# LED-controller-4.net
KiCad netlist of a schematic drawn in EAGLE
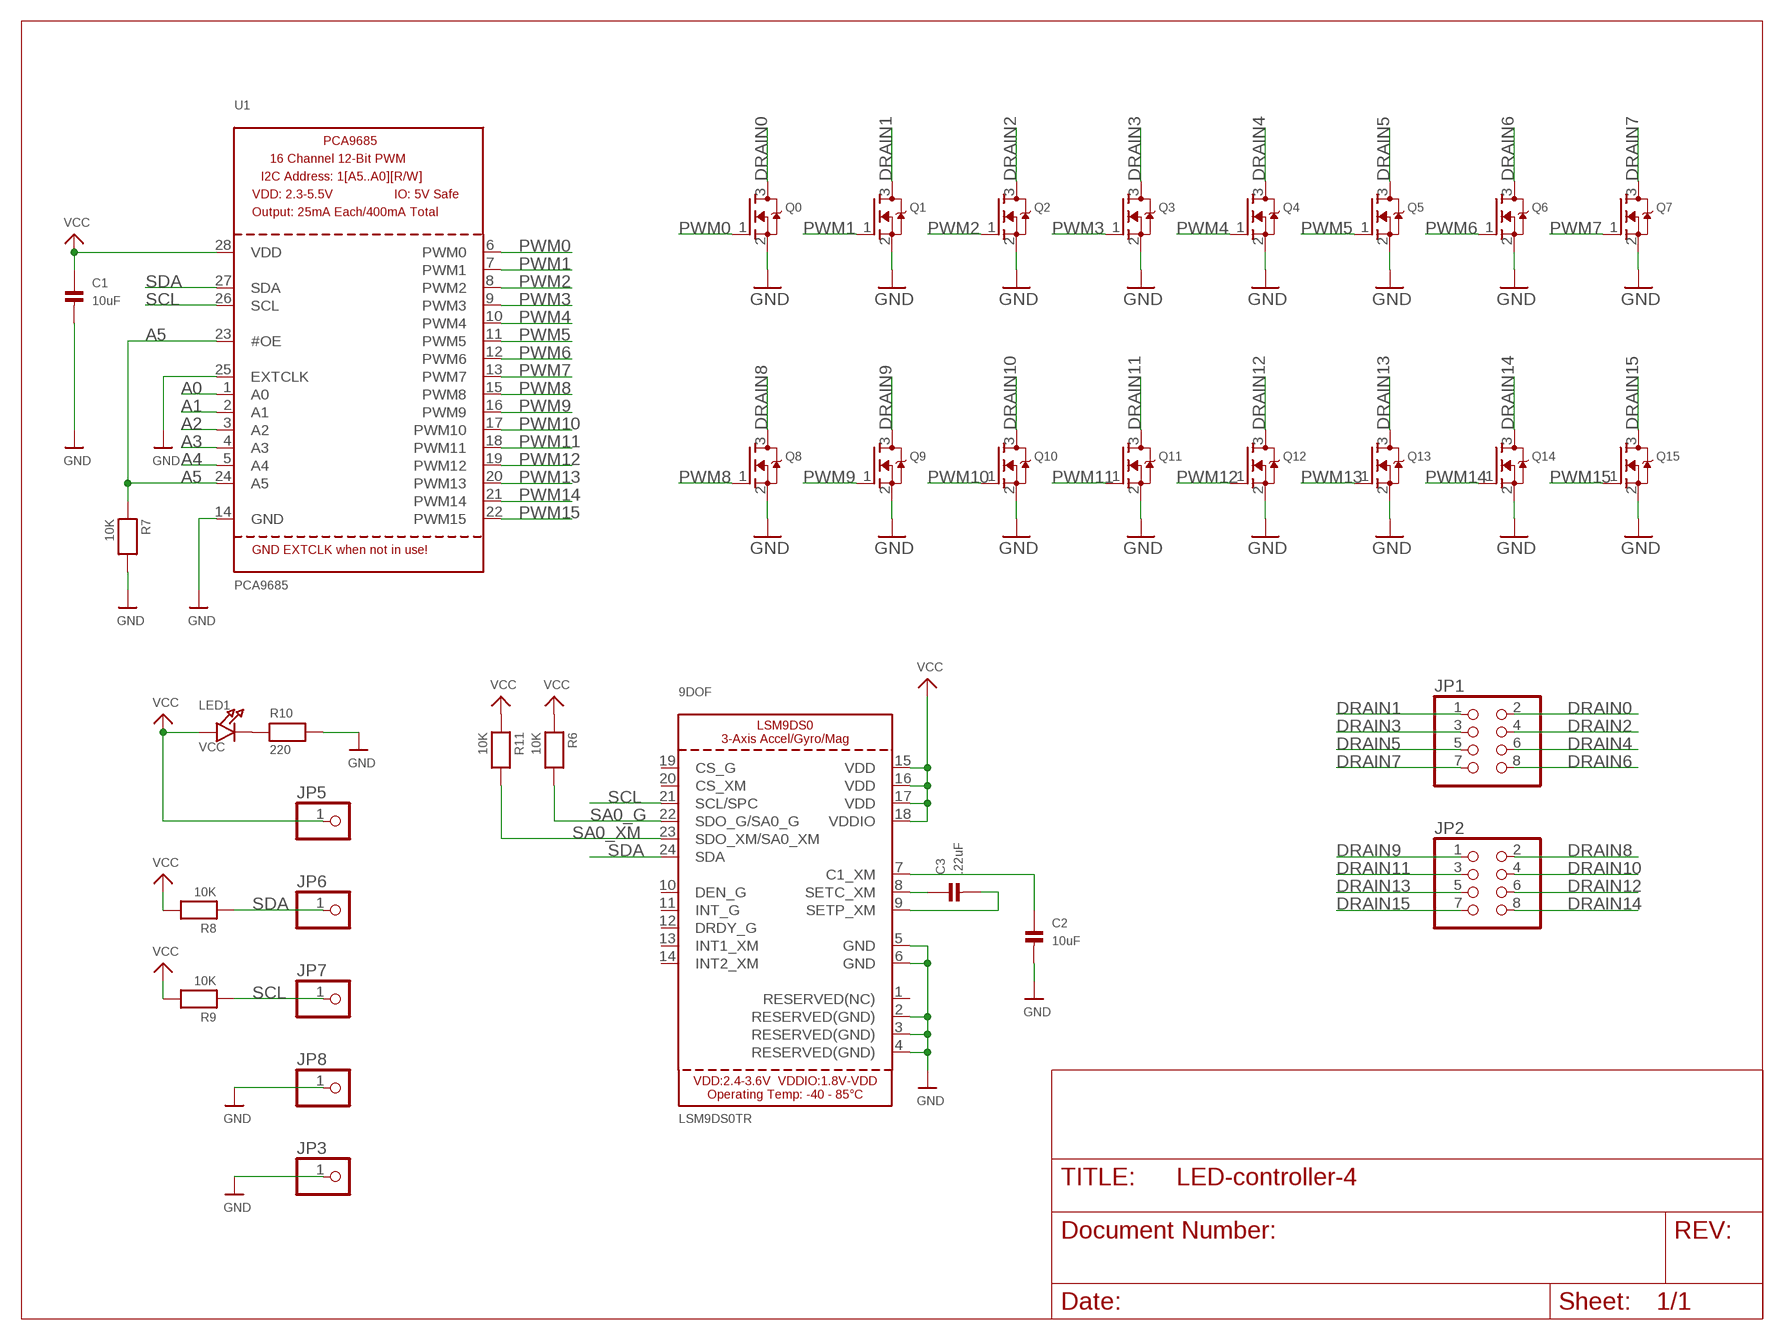
[diagram p0: schematic, sheet 1]

(export (version "E")
  (design (tool "Eeschema 10.0.6"))
  (components
    (comp (ref "9DOF")
      (value "LSM9DS0TR")
      (footprint "eagle-import:LGA24_4X4MM")
      (libsource (lib "eagle-import") (part "LSM9DS0"))
    )
    (comp (ref "C1")
      (value "10uF")
      (footprint "eagle-import:0805")
      (libsource (lib "eagle-import") (part "CAP_CERAMIC0805"))
    )
    (comp (ref "C2")
      (value "10uF")
      (footprint "eagle-import:0805")
      (libsource (lib "eagle-import") (part "CAP_CERAMIC0805"))
    )
    (comp (ref "C3")
      (value ".22uF")
      (footprint "eagle-import:0805")
      (libsource (lib "eagle-import") (part "CAP_CERAMIC0805"))
    )
    (comp (ref "JP1")
      (value "PINHD-2X4")
      (footprint "eagle-import:2X04")
      (libsource (lib "eagle-import") (part "PINHD-2X4"))
    )
    (comp (ref "JP2")
      (value "PINHD-2X4")
      (footprint "eagle-import:2X04")
      (libsource (lib "eagle-import") (part "PINHD-2X4"))
    )
    (comp (ref "JP3")
      (value "PINHD-1X1CB")
      (footprint "eagle-import:1X01-CLEANBIG")
      (libsource (lib "eagle-import") (part "PINHD-1X1CB"))
    )
    (comp (ref "JP5")
      (value "PINHD-1X1CB")
      (footprint "eagle-import:1X01-CLEANBIG")
      (libsource (lib "eagle-import") (part "PINHD-1X1CB"))
    )
    (comp (ref "JP6")
      (value "PINHD-1X1CB")
      (footprint "eagle-import:1X01-CLEANBIG")
      (libsource (lib "eagle-import") (part "PINHD-1X1CB"))
    )
    (comp (ref "JP7")
      (value "PINHD-1X1CB")
      (footprint "eagle-import:1X01-CLEANBIG")
      (libsource (lib "eagle-import") (part "PINHD-1X1CB"))
    )
    (comp (ref "JP8")
      (value "PINHD-1X1CB")
      (footprint "eagle-import:1X01-CLEANBIG")
      (libsource (lib "eagle-import") (part "PINHD-1X1CB"))
    )
    (comp (ref "LED1")
      (value "VCC")
      (footprint "eagle-import:CHIPLED_0805")
      (libsource (lib "eagle-import") (part "LED0805"))
    )
    (comp (ref "Q0")
      (value "MOSFET-NREFLOW")
      (footprint "eagle-import:SOT23")
      (libsource (lib "eagle-import") (part "MOSFET-NREFLOW"))
    )
    (comp (ref "Q1")
      (value "MOSFET-NREFLOW")
      (footprint "eagle-import:SOT23")
      (libsource (lib "eagle-import") (part "MOSFET-NREFLOW"))
    )
    (comp (ref "Q2")
      (value "MOSFET-NREFLOW")
      (footprint "eagle-import:SOT23")
      (libsource (lib "eagle-import") (part "MOSFET-NREFLOW"))
    )
    (comp (ref "Q3")
      (value "MOSFET-NREFLOW")
      (footprint "eagle-import:SOT23")
      (libsource (lib "eagle-import") (part "MOSFET-NREFLOW"))
    )
    (comp (ref "Q4")
      (value "MOSFET-NREFLOW")
      (footprint "eagle-import:SOT23")
      (libsource (lib "eagle-import") (part "MOSFET-NREFLOW"))
    )
    (comp (ref "Q5")
      (value "MOSFET-NREFLOW")
      (footprint "eagle-import:SOT23")
      (libsource (lib "eagle-import") (part "MOSFET-NREFLOW"))
    )
    (comp (ref "Q6")
      (value "MOSFET-NREFLOW")
      (footprint "eagle-import:SOT23")
      (libsource (lib "eagle-import") (part "MOSFET-NREFLOW"))
    )
    (comp (ref "Q7")
      (value "MOSFET-NREFLOW")
      (footprint "eagle-import:SOT23")
      (libsource (lib "eagle-import") (part "MOSFET-NREFLOW"))
    )
    (comp (ref "Q8")
      (value "MOSFET-NREFLOW")
      (footprint "eagle-import:SOT23")
      (libsource (lib "eagle-import") (part "MOSFET-NREFLOW"))
    )
    (comp (ref "Q9")
      (value "MOSFET-NREFLOW")
      (footprint "eagle-import:SOT23")
      (libsource (lib "eagle-import") (part "MOSFET-NREFLOW"))
    )
    (comp (ref "Q10")
      (value "MOSFET-NREFLOW")
      (footprint "eagle-import:SOT23")
      (libsource (lib "eagle-import") (part "MOSFET-NREFLOW"))
    )
    (comp (ref "Q11")
      (value "MOSFET-NREFLOW")
      (footprint "eagle-import:SOT23")
      (libsource (lib "eagle-import") (part "MOSFET-NREFLOW"))
    )
    (comp (ref "Q12")
      (value "MOSFET-NREFLOW")
      (footprint "eagle-import:SOT23")
      (libsource (lib "eagle-import") (part "MOSFET-NREFLOW"))
    )
    (comp (ref "Q13")
      (value "MOSFET-NREFLOW")
      (footprint "eagle-import:SOT23")
      (libsource (lib "eagle-import") (part "MOSFET-NREFLOW"))
    )
    (comp (ref "Q14")
      (value "MOSFET-NREFLOW")
      (footprint "eagle-import:SOT23")
      (libsource (lib "eagle-import") (part "MOSFET-NREFLOW"))
    )
    (comp (ref "Q15")
      (value "MOSFET-NREFLOW")
      (footprint "eagle-import:SOT23")
      (libsource (lib "eagle-import") (part "MOSFET-NREFLOW"))
    )
    (comp (ref "R6")
      (value "10K")
      (footprint "eagle-import:0603")
      (libsource (lib "eagle-import") (part "RESISTOR0603"))
    )
    (comp (ref "R7")
      (value "10K")
      (footprint "eagle-import:0603")
      (libsource (lib "eagle-import") (part "RESISTOR0603"))
    )
    (comp (ref "R8")
      (value "10K")
      (footprint "eagle-import:0603")
      (libsource (lib "eagle-import") (part "RESISTOR0603"))
    )
    (comp (ref "R9")
      (value "10K")
      (footprint "eagle-import:0603")
      (libsource (lib "eagle-import") (part "RESISTOR0603"))
    )
    (comp (ref "R10")
      (value "220")
      (footprint "eagle-import:0603")
      (libsource (lib "eagle-import") (part "RESISTOR0603"))
    )
    (comp (ref "R11")
      (value "10K")
      (footprint "eagle-import:0603")
      (libsource (lib "eagle-import") (part "RESISTOR0603"))
    )
    (comp (ref "U1")
      (value "PCA9685")
      (footprint "eagle-import:TSSOP28")
      (libsource (lib "eagle-import") (part "PCA9685"))
    )
  )
  (nets
    (net (code "1") (name "/A0") (class "Default")
      (node (ref "U1") (pin "1") (pinfunction "A0_1") (pintype "bidirectional"))
    )
    (net (code "2") (name "/A1") (class "Default")
      (node (ref "U1") (pin "2") (pinfunction "A1_2") (pintype "bidirectional"))
    )
    (net (code "3") (name "/A2") (class "Default")
      (node (ref "U1") (pin "3") (pinfunction "A2_3") (pintype "bidirectional"))
    )
    (net (code "4") (name "/A3") (class "Default")
      (node (ref "U1") (pin "4") (pinfunction "A3_4") (pintype "bidirectional"))
    )
    (net (code "5") (name "/A4") (class "Default")
      (node (ref "U1") (pin "5") (pinfunction "A4_5") (pintype "bidirectional"))
    )
    (net (code "6") (name "/A5") (class "Default")
      (node (ref "R7") (pin "1") (pinfunction "1_1") (pintype "passive"))
      (node (ref "U1") (pin "23") (pinfunction "#OE_23") (pintype "input"))
      (node (ref "U1") (pin "24") (pinfunction "A5_24") (pintype "bidirectional"))
    )
    (net (code "7") (name "/DRAIN0") (class "Default")
      (node (ref "JP1") (pin "2") (pinfunction "2_2") (pintype "passive"))
      (node (ref "Q0") (pin "3") (pinfunction "D_3") (pintype "bidirectional"))
    )
    (net (code "8") (name "/DRAIN1") (class "Default")
      (node (ref "JP1") (pin "1") (pinfunction "1_1") (pintype "passive"))
      (node (ref "Q1") (pin "3") (pinfunction "D_3") (pintype "bidirectional"))
    )
    (net (code "9") (name "/DRAIN2") (class "Default")
      (node (ref "JP1") (pin "4") (pinfunction "4_4") (pintype "passive"))
      (node (ref "Q2") (pin "3") (pinfunction "D_3") (pintype "bidirectional"))
    )
    (net (code "10") (name "/DRAIN3") (class "Default")
      (node (ref "JP1") (pin "3") (pinfunction "3_3") (pintype "passive"))
      (node (ref "Q3") (pin "3") (pinfunction "D_3") (pintype "bidirectional"))
    )
    (net (code "11") (name "/DRAIN4") (class "Default")
      (node (ref "JP1") (pin "6") (pinfunction "6_6") (pintype "passive"))
      (node (ref "Q4") (pin "3") (pinfunction "D_3") (pintype "bidirectional"))
    )
    (net (code "12") (name "/DRAIN5") (class "Default")
      (node (ref "JP1") (pin "5") (pinfunction "5_5") (pintype "passive"))
      (node (ref "Q5") (pin "3") (pinfunction "D_3") (pintype "bidirectional"))
    )
    (net (code "13") (name "/DRAIN6") (class "Default")
      (node (ref "JP1") (pin "8") (pinfunction "8_8") (pintype "passive"))
      (node (ref "Q6") (pin "3") (pinfunction "D_3") (pintype "bidirectional"))
    )
    (net (code "14") (name "/DRAIN7") (class "Default")
      (node (ref "JP1") (pin "7") (pinfunction "7_7") (pintype "passive"))
      (node (ref "Q7") (pin "3") (pinfunction "D_3") (pintype "bidirectional"))
    )
    (net (code "15") (name "/DRAIN8") (class "Default")
      (node (ref "JP2") (pin "2") (pinfunction "2_2") (pintype "passive"))
      (node (ref "Q8") (pin "3") (pinfunction "D_3") (pintype "bidirectional"))
    )
    (net (code "16") (name "/DRAIN9") (class "Default")
      (node (ref "JP2") (pin "1") (pinfunction "1_1") (pintype "passive"))
      (node (ref "Q9") (pin "3") (pinfunction "D_3") (pintype "bidirectional"))
    )
    (net (code "17") (name "/DRAIN10") (class "Default")
      (node (ref "JP2") (pin "4") (pinfunction "4_4") (pintype "passive"))
      (node (ref "Q10") (pin "3") (pinfunction "D_3") (pintype "bidirectional"))
    )
    (net (code "18") (name "/DRAIN11") (class "Default")
      (node (ref "JP2") (pin "3") (pinfunction "3_3") (pintype "passive"))
      (node (ref "Q11") (pin "3") (pinfunction "D_3") (pintype "bidirectional"))
    )
    (net (code "19") (name "/DRAIN12") (class "Default")
      (node (ref "JP2") (pin "6") (pinfunction "6_6") (pintype "passive"))
      (node (ref "Q12") (pin "3") (pinfunction "D_3") (pintype "bidirectional"))
    )
    (net (code "20") (name "/DRAIN13") (class "Default")
      (node (ref "JP2") (pin "5") (pinfunction "5_5") (pintype "passive"))
      (node (ref "Q13") (pin "3") (pinfunction "D_3") (pintype "bidirectional"))
    )
    (net (code "21") (name "/DRAIN14") (class "Default")
      (node (ref "JP2") (pin "8") (pinfunction "8_8") (pintype "passive"))
      (node (ref "Q14") (pin "3") (pinfunction "D_3") (pintype "bidirectional"))
    )
    (net (code "22") (name "/DRAIN15") (class "Default")
      (node (ref "JP2") (pin "7") (pinfunction "7_7") (pintype "passive"))
      (node (ref "Q15") (pin "3") (pinfunction "D_3") (pintype "bidirectional"))
    )
    (net (code "23") (name "/PWM0") (class "Default")
      (node (ref "Q0") (pin "1") (pinfunction "G_1") (pintype "bidirectional"))
      (node (ref "U1") (pin "6") (pinfunction "PWM0_6") (pintype "output"))
    )
    (net (code "24") (name "/PWM1") (class "Default")
      (node (ref "Q1") (pin "1") (pinfunction "G_1") (pintype "bidirectional"))
      (node (ref "U1") (pin "7") (pinfunction "PWM1_7") (pintype "output"))
    )
    (net (code "25") (name "/PWM2") (class "Default")
      (node (ref "Q2") (pin "1") (pinfunction "G_1") (pintype "bidirectional"))
      (node (ref "U1") (pin "8") (pinfunction "PWM2_8") (pintype "output"))
    )
    (net (code "26") (name "/PWM3") (class "Default")
      (node (ref "Q3") (pin "1") (pinfunction "G_1") (pintype "bidirectional"))
      (node (ref "U1") (pin "9") (pinfunction "PWM3_9") (pintype "output"))
    )
    (net (code "27") (name "/PWM4") (class "Default")
      (node (ref "Q4") (pin "1") (pinfunction "G_1") (pintype "bidirectional"))
      (node (ref "U1") (pin "10") (pinfunction "PWM4_10") (pintype "output"))
    )
    (net (code "28") (name "/PWM5") (class "Default")
      (node (ref "Q5") (pin "1") (pinfunction "G_1") (pintype "bidirectional"))
      (node (ref "U1") (pin "11") (pinfunction "PWM5_11") (pintype "output"))
    )
    (net (code "29") (name "/PWM6") (class "Default")
      (node (ref "Q6") (pin "1") (pinfunction "G_1") (pintype "bidirectional"))
      (node (ref "U1") (pin "12") (pinfunction "PWM6_12") (pintype "output"))
    )
    (net (code "30") (name "/PWM7") (class "Default")
      (node (ref "Q7") (pin "1") (pinfunction "G_1") (pintype "bidirectional"))
      (node (ref "U1") (pin "13") (pinfunction "PWM7_13") (pintype "output"))
    )
    (net (code "31") (name "/PWM8") (class "Default")
      (node (ref "Q8") (pin "1") (pinfunction "G_1") (pintype "bidirectional"))
      (node (ref "U1") (pin "15") (pinfunction "PWM8_15") (pintype "output"))
    )
    (net (code "32") (name "/PWM9") (class "Default")
      (node (ref "Q9") (pin "1") (pinfunction "G_1") (pintype "bidirectional"))
      (node (ref "U1") (pin "16") (pinfunction "PWM9_16") (pintype "output"))
    )
    (net (code "33") (name "/PWM10") (class "Default")
      (node (ref "Q10") (pin "1") (pinfunction "G_1") (pintype "bidirectional"))
      (node (ref "U1") (pin "17") (pinfunction "PWM10_17") (pintype "output"))
    )
    (net (code "34") (name "/PWM11") (class "Default")
      (node (ref "Q11") (pin "1") (pinfunction "G_1") (pintype "bidirectional"))
      (node (ref "U1") (pin "18") (pinfunction "PWM11_18") (pintype "output"))
    )
    (net (code "35") (name "/PWM12") (class "Default")
      (node (ref "Q12") (pin "1") (pinfunction "G_1") (pintype "bidirectional"))
      (node (ref "U1") (pin "19") (pinfunction "PWM12_19") (pintype "output"))
    )
    (net (code "36") (name "/PWM13") (class "Default")
      (node (ref "Q13") (pin "1") (pinfunction "G_1") (pintype "bidirectional"))
      (node (ref "U1") (pin "20") (pinfunction "PWM13_20") (pintype "output"))
    )
    (net (code "37") (name "/PWM14") (class "Default")
      (node (ref "Q14") (pin "1") (pinfunction "G_1") (pintype "bidirectional"))
      (node (ref "U1") (pin "21") (pinfunction "PWM14_21") (pintype "output"))
    )
    (net (code "38") (name "/PWM15") (class "Default")
      (node (ref "Q15") (pin "1") (pinfunction "G_1") (pintype "bidirectional"))
      (node (ref "U1") (pin "22") (pinfunction "PWM15_22") (pintype "output"))
    )
    (net (code "39") (name "/SA0_G") (class "Default")
      (node (ref "9DOF") (pin "22") (pinfunction "SDO_G/SA0_G_22") (pintype "bidirectional"))
      (node (ref "R6") (pin "2") (pinfunction "2_2") (pintype "passive"))
    )
    (net (code "40") (name "/SA0_XM") (class "Default")
      (node (ref "9DOF") (pin "23") (pinfunction "SDO_XM/SA0_XM_23") (pintype "bidirectional"))
      (node (ref "R11") (pin "2") (pinfunction "2_2") (pintype "passive"))
    )
    (net (code "41") (name "/SCL") (class "Default")
      (node (ref "9DOF") (pin "21") (pinfunction "SCL/SPC_21") (pintype "bidirectional"))
      (node (ref "JP7") (pin "1") (pinfunction "1_1") (pintype "passive"))
      (node (ref "R9") (pin "1") (pinfunction "1_1") (pintype "passive"))
      (node (ref "U1") (pin "26") (pinfunction "SCL_26") (pintype "bidirectional"))
    )
    (net (code "42") (name "/SDA") (class "Default")
      (node (ref "9DOF") (pin "24") (pinfunction "SDA_24") (pintype "bidirectional"))
      (node (ref "JP6") (pin "1") (pinfunction "1_1") (pintype "passive"))
      (node (ref "R8") (pin "1") (pinfunction "1_1") (pintype "passive"))
      (node (ref "U1") (pin "27") (pinfunction "SDA_27") (pintype "bidirectional"))
    )
    (net (code "43") (name "GND") (class "Default")
      (node (ref "9DOF") (pin "2") (pinfunction "RESERVED(GND)_2") (pintype "power_in"))
      (node (ref "9DOF") (pin "3") (pinfunction "RESERVED(GND)_3") (pintype "power_in"))
      (node (ref "9DOF") (pin "4") (pinfunction "RESERVED(GND)_4") (pintype "power_in"))
      (node (ref "9DOF") (pin "5") (pinfunction "GND_5") (pintype "power_in"))
      (node (ref "9DOF") (pin "6") (pinfunction "GND_6") (pintype "power_in"))
      (node (ref "C1") (pin "2") (pinfunction "P$2_2") (pintype "passive"))
      (node (ref "C2") (pin "2") (pinfunction "P$2_2") (pintype "passive"))
      (node (ref "JP3") (pin "1") (pinfunction "1_1") (pintype "passive"))
      (node (ref "JP8") (pin "1") (pinfunction "1_1") (pintype "passive"))
      (node (ref "Q0") (pin "2") (pinfunction "S_2") (pintype "bidirectional"))
      (node (ref "Q1") (pin "2") (pinfunction "S_2") (pintype "bidirectional"))
      (node (ref "Q10") (pin "2") (pinfunction "S_2") (pintype "bidirectional"))
      (node (ref "Q11") (pin "2") (pinfunction "S_2") (pintype "bidirectional"))
      (node (ref "Q12") (pin "2") (pinfunction "S_2") (pintype "bidirectional"))
      (node (ref "Q13") (pin "2") (pinfunction "S_2") (pintype "bidirectional"))
      (node (ref "Q14") (pin "2") (pinfunction "S_2") (pintype "bidirectional"))
      (node (ref "Q15") (pin "2") (pinfunction "S_2") (pintype "bidirectional"))
      (node (ref "Q2") (pin "2") (pinfunction "S_2") (pintype "bidirectional"))
      (node (ref "Q3") (pin "2") (pinfunction "S_2") (pintype "bidirectional"))
      (node (ref "Q4") (pin "2") (pinfunction "S_2") (pintype "bidirectional"))
      (node (ref "Q5") (pin "2") (pinfunction "S_2") (pintype "bidirectional"))
      (node (ref "Q6") (pin "2") (pinfunction "S_2") (pintype "bidirectional"))
      (node (ref "Q7") (pin "2") (pinfunction "S_2") (pintype "bidirectional"))
      (node (ref "Q8") (pin "2") (pinfunction "S_2") (pintype "bidirectional"))
      (node (ref "Q9") (pin "2") (pinfunction "S_2") (pintype "bidirectional"))
      (node (ref "R10") (pin "2") (pinfunction "2_2") (pintype "passive"))
      (node (ref "R7") (pin "2") (pinfunction "2_2") (pintype "passive"))
      (node (ref "U1") (pin "14") (pinfunction "GND_14") (pintype "power_in"))
      (node (ref "U1") (pin "25") (pinfunction "EXTCLK_25") (pintype "input"))
    )
    (net (code "44") (name "Net-(9DOF-C1_XM)") (class "Default")
      (node (ref "9DOF") (pin "7") (pinfunction "C1_XM_7") (pintype "bidirectional"))
      (node (ref "C2") (pin "1") (pinfunction "P$1_1") (pintype "passive"))
    )
    (net (code "45") (name "Net-(9DOF-SETC_XM)") (class "Default")
      (node (ref "9DOF") (pin "8") (pinfunction "SETC_XM_8") (pintype "bidirectional"))
      (node (ref "C3") (pin "1") (pinfunction "P$1_1") (pintype "passive"))
    )
    (net (code "46") (name "Net-(9DOF-SETP_XM)") (class "Default")
      (node (ref "9DOF") (pin "9") (pinfunction "SETP_XM_9") (pintype "bidirectional"))
      (node (ref "C3") (pin "2") (pinfunction "P$2_2") (pintype "passive"))
    )
    (net (code "47") (name "Net-(LED1-PadC)") (class "Default")
      (node (ref "LED1") (pin "C") (pinfunction "C_C") (pintype "passive"))
      (node (ref "R10") (pin "1") (pinfunction "1_1") (pintype "passive"))
    )
    (net (code "48") (name "VCC") (class "Default")
      (node (ref "9DOF") (pin "15") (pinfunction "VDD_15") (pintype "power_in"))
      (node (ref "9DOF") (pin "16") (pinfunction "VDD_16") (pintype "power_in"))
      (node (ref "9DOF") (pin "17") (pinfunction "VDD_17") (pintype "power_in"))
      (node (ref "9DOF") (pin "18") (pinfunction "VDDIO_18") (pintype "power_in"))
      (node (ref "C1") (pin "1") (pinfunction "P$1_1") (pintype "passive"))
      (node (ref "JP5") (pin "1") (pinfunction "1_1") (pintype "passive"))
      (node (ref "LED1") (pin "A") (pinfunction "A_A") (pintype "passive"))
      (node (ref "R11") (pin "1") (pinfunction "1_1") (pintype "passive"))
      (node (ref "R6") (pin "1") (pinfunction "1_1") (pintype "passive"))
      (node (ref "R8") (pin "2") (pinfunction "2_2") (pintype "passive"))
      (node (ref "R9") (pin "2") (pinfunction "2_2") (pintype "passive"))
      (node (ref "U1") (pin "28") (pinfunction "VDD_28") (pintype "power_in"))
    )
    (net (code "49") (name "unconnected-(9DOF-CS_G-Pad19)") (class "Default")
      (node (ref "9DOF") (pin "19") (pinfunction "CS_G_19") (pintype "bidirectional"))
    )
    (net (code "50") (name "unconnected-(9DOF-CS_XM-Pad20)") (class "Default")
      (node (ref "9DOF") (pin "20") (pinfunction "CS_XM_20") (pintype "bidirectional"))
    )
    (net (code "51") (name "unconnected-(9DOF-DEN_G-Pad10)") (class "Default")
      (node (ref "9DOF") (pin "10") (pinfunction "DEN_G_10") (pintype "bidirectional"))
    )
    (net (code "52") (name "unconnected-(9DOF-DRDY_G-Pad12)") (class "Default")
      (node (ref "9DOF") (pin "12") (pinfunction "DRDY_G_12") (pintype "bidirectional"))
    )
    (net (code "53") (name "unconnected-(9DOF-INT1_XM-Pad13)") (class "Default")
      (node (ref "9DOF") (pin "13") (pinfunction "INT1_XM_13") (pintype "bidirectional"))
    )
    (net (code "54") (name "unconnected-(9DOF-INT2_XM-Pad14)") (class "Default")
      (node (ref "9DOF") (pin "14") (pinfunction "INT2_XM_14") (pintype "bidirectional"))
    )
    (net (code "55") (name "unconnected-(9DOF-INT_G-Pad11)") (class "Default")
      (node (ref "9DOF") (pin "11") (pinfunction "INT_G_11") (pintype "bidirectional"))
    )
    (net (code "56") (name "unconnected-(9DOF-RESERVED(NC)-Pad1)") (class "Default")
      (node (ref "9DOF") (pin "1") (pinfunction "RESERVED(NC)_1") (pintype "no_connect"))
    )
  )
)
